# carte_alim.net
KiCad netlist of a schematic drawn in EAGLE
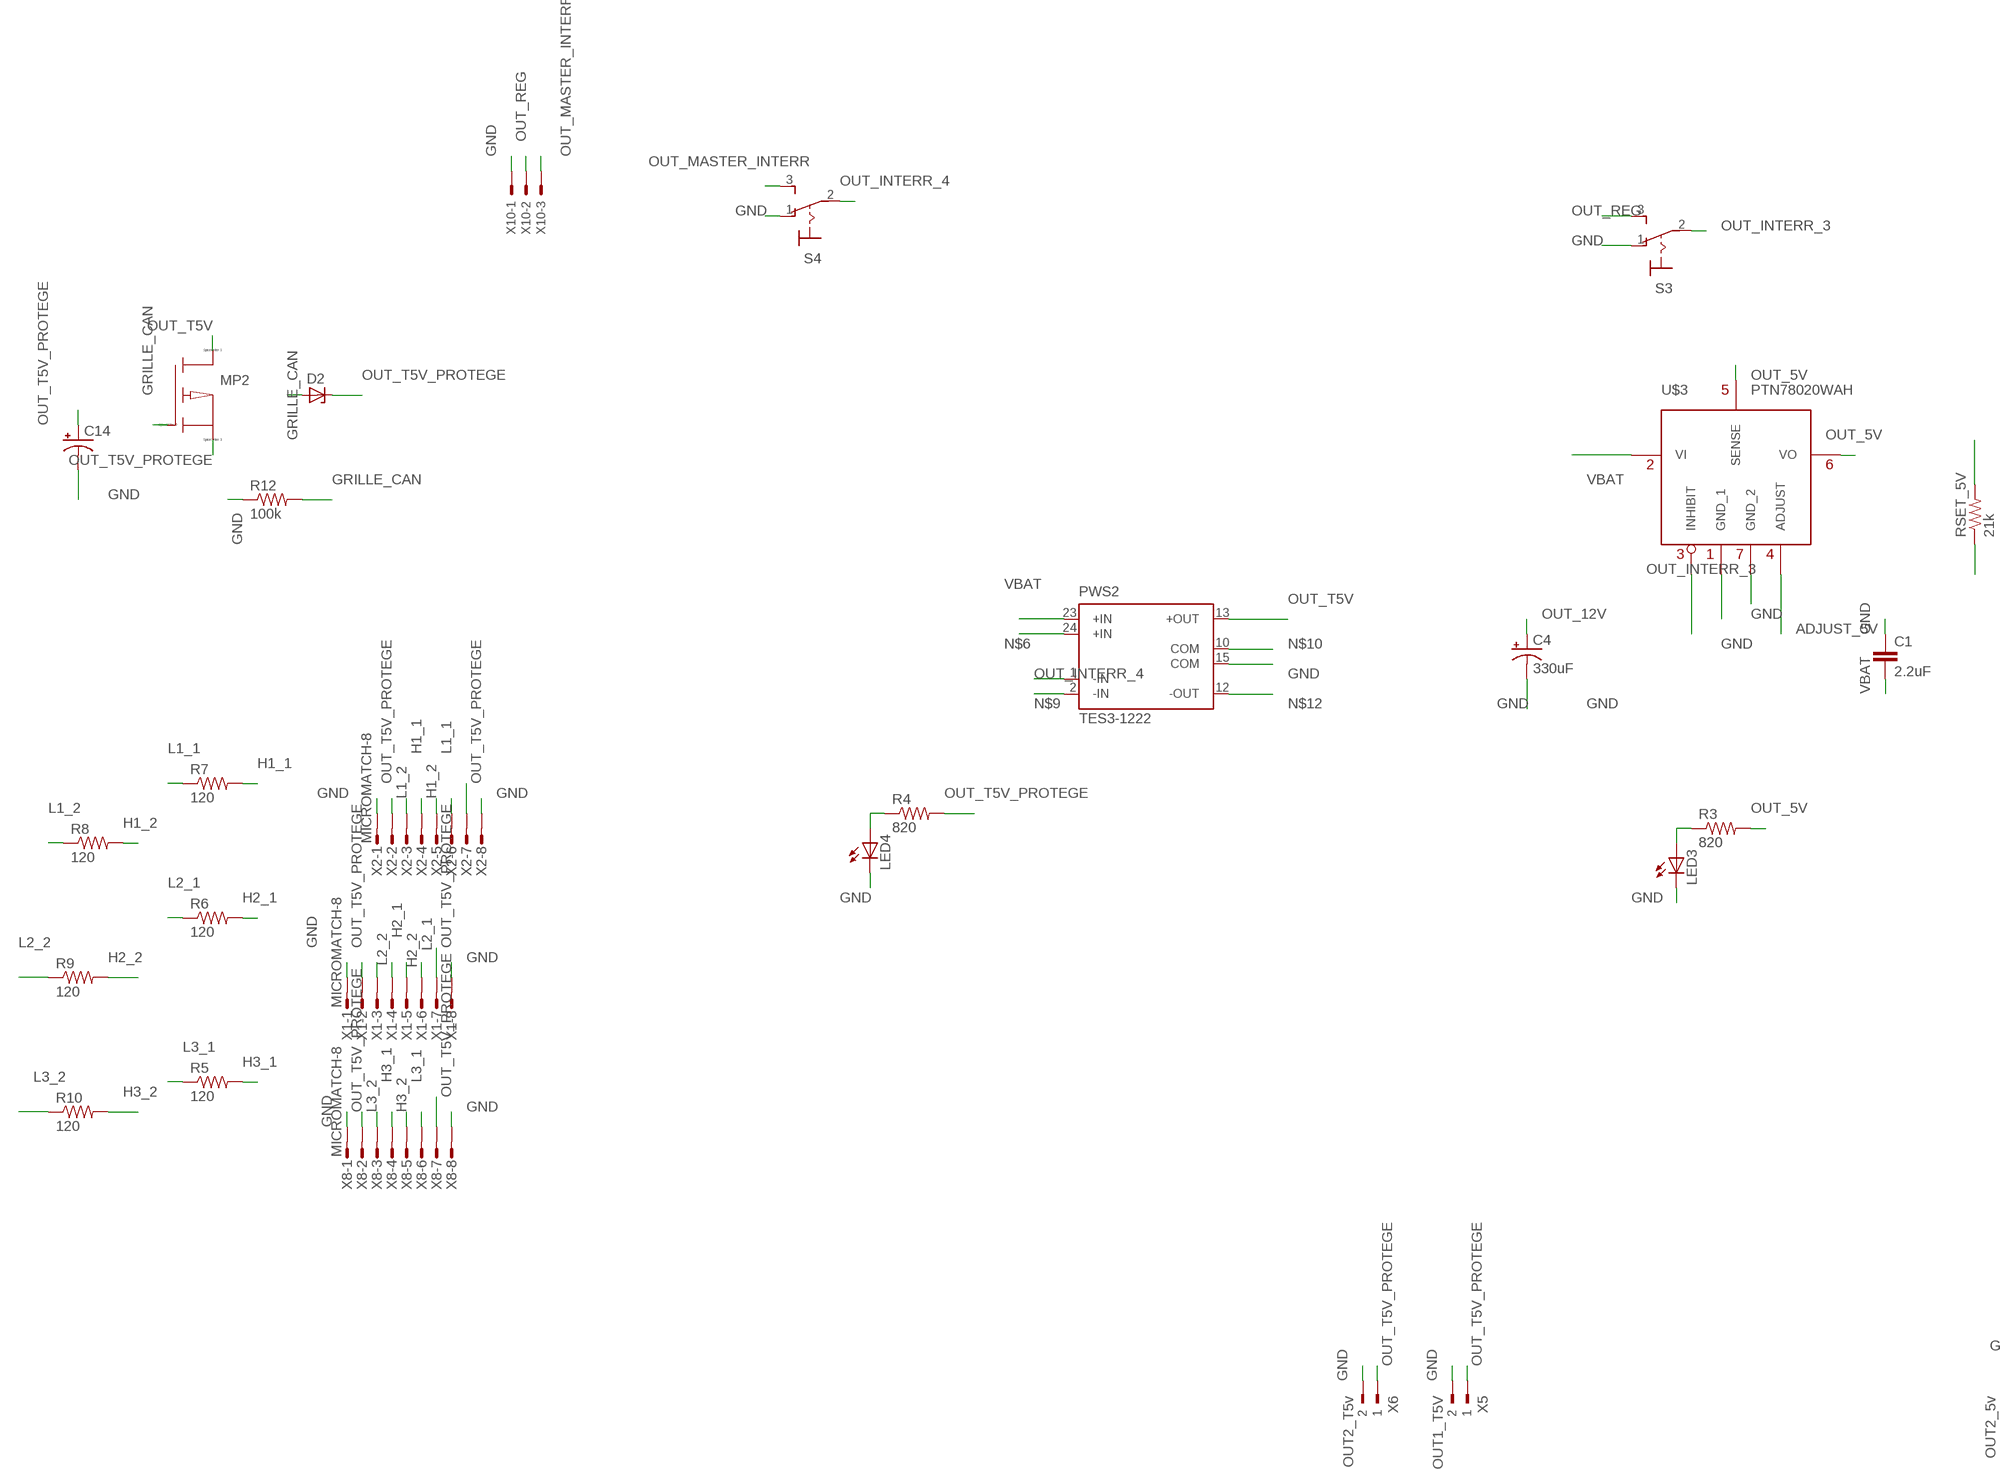
[diagram p0: schematic, sheet 1, part 1 of 2]
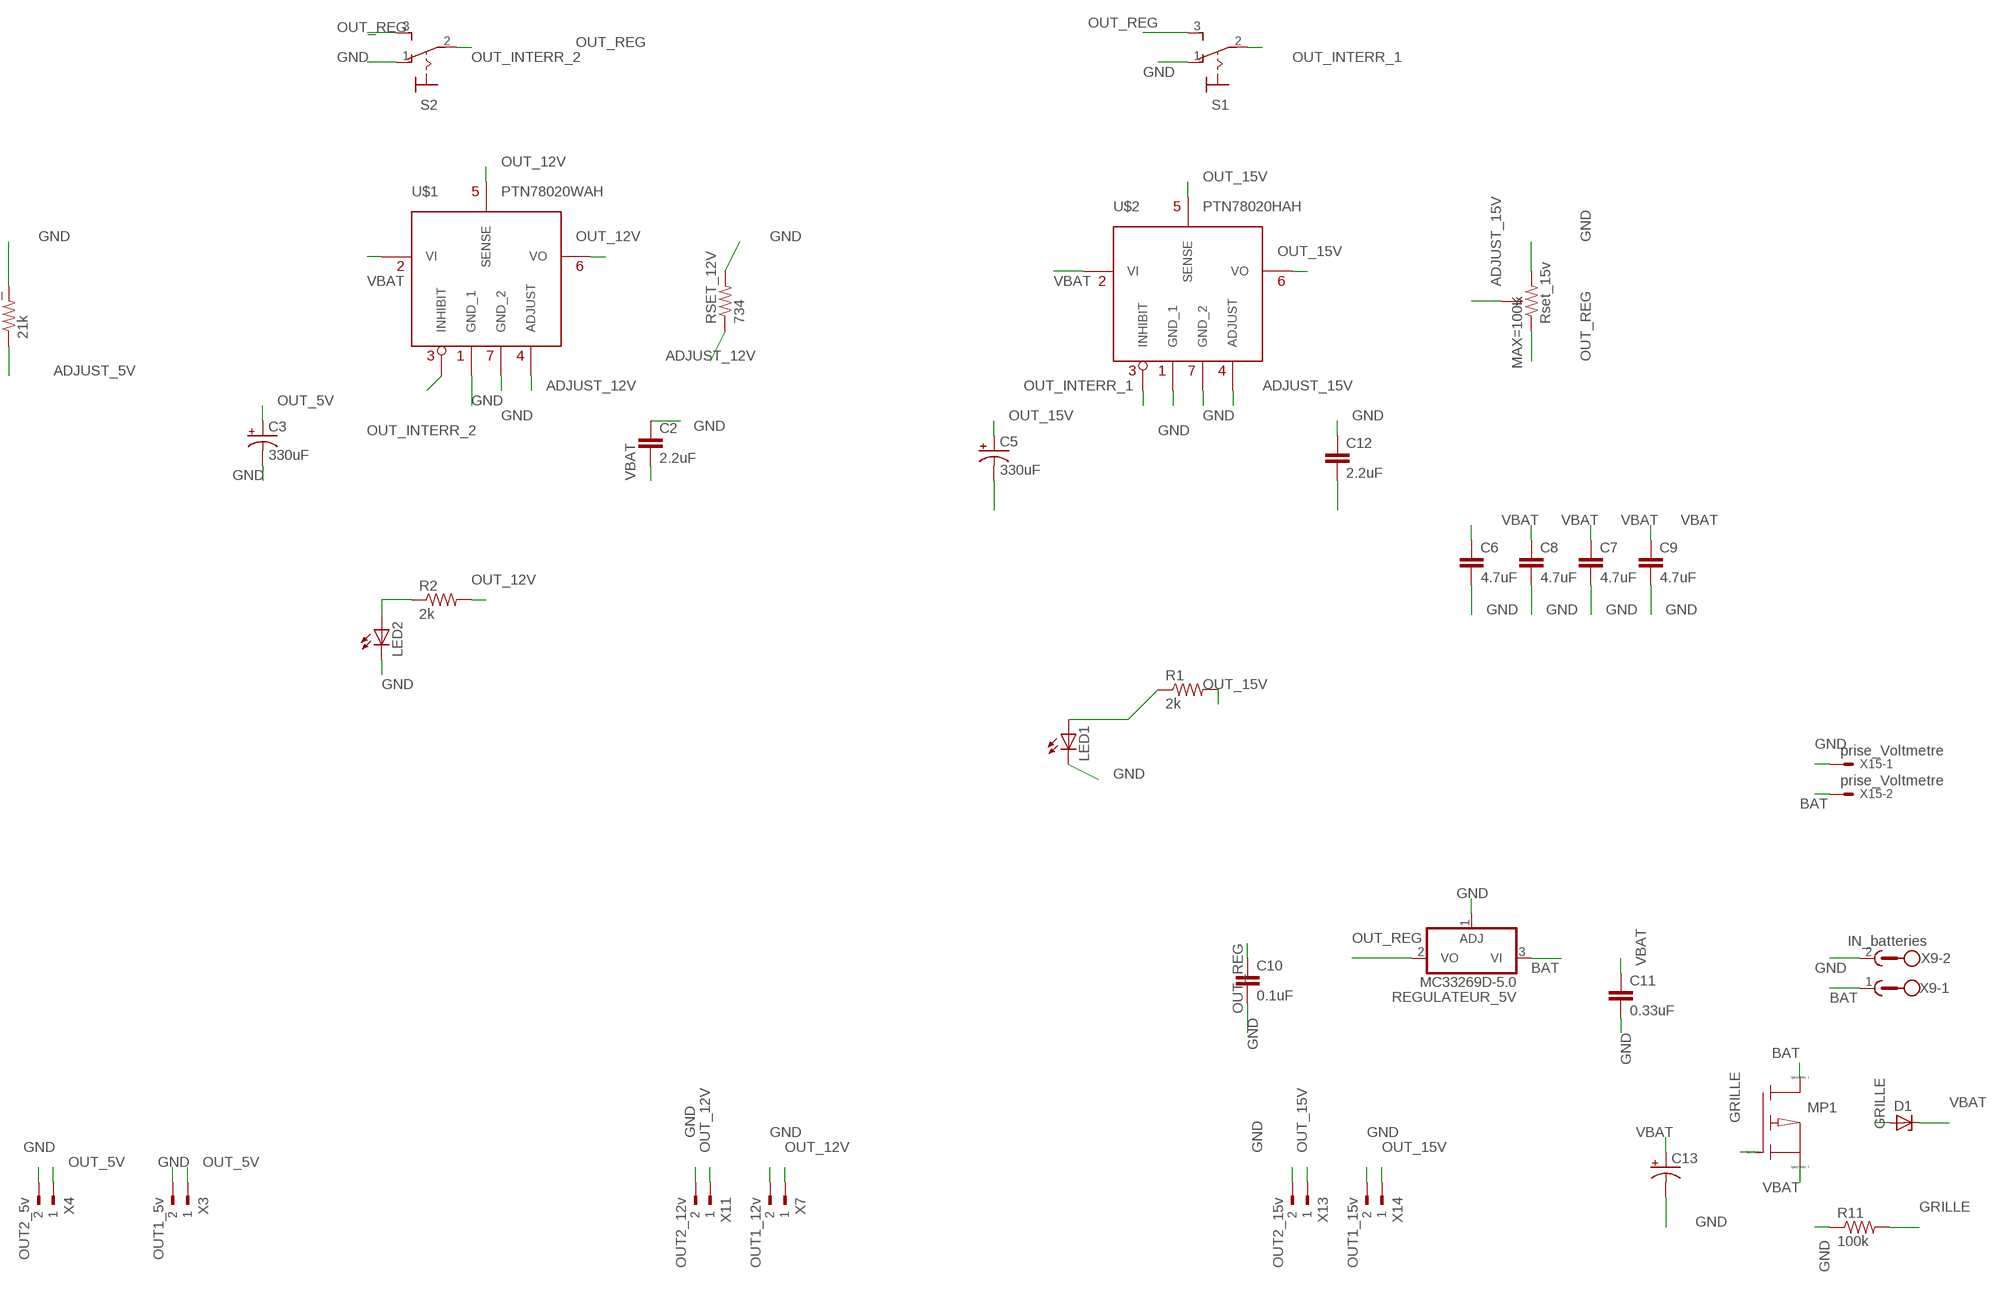
[diagram p1: schematic, sheet 1, part 2 of 2]

(export (version "E")
  (design (tool "Eeschema 10.0.6"))
  (components
    (comp (ref "C1")
      (value "2.2uF")
      (footprint "eagle-import:0805")
      (libsource (lib "eagle-import") (part "CAP0805"))
    )
    (comp (ref "C2")
      (value "2.2uF")
      (footprint "eagle-import:0805")
      (libsource (lib "eagle-import") (part "CAP0805"))
    )
    (comp (ref "C3")
      (value "330uF")
      (footprint "eagle-import:CPOL-RADIAL-100UF-25V")
      (libsource (lib "eagle-import") (part "CAP_POLPTH1"))
    )
    (comp (ref "C4")
      (value "330uF")
      (footprint "eagle-import:CPOL-RADIAL-100UF-25V")
      (libsource (lib "eagle-import") (part "CAP_POLPTH1"))
    )
    (comp (ref "C5")
      (value "330uF")
      (footprint "eagle-import:CPOL-RADIAL-100UF-25V")
      (libsource (lib "eagle-import") (part "CAP_POLPTH1"))
    )
    (comp (ref "C6")
      (value "4.7uF")
      (footprint "eagle-import:0805")
      (libsource (lib "eagle-import") (part "CAP0805"))
    )
    (comp (ref "C7")
      (value "4.7uF")
      (footprint "eagle-import:0805")
      (libsource (lib "eagle-import") (part "CAP0805"))
    )
    (comp (ref "C8")
      (value "4.7uF")
      (footprint "eagle-import:0805")
      (libsource (lib "eagle-import") (part "CAP0805"))
    )
    (comp (ref "C9")
      (value "4.7uF")
      (footprint "eagle-import:0805")
      (libsource (lib "eagle-import") (part "CAP0805"))
    )
    (comp (ref "C10")
      (value "0.1uF")
      (footprint "eagle-import:0805")
      (libsource (lib "eagle-import") (part "CAP0805"))
    )
    (comp (ref "C11")
      (value "0.33uF")
      (footprint "eagle-import:0805")
      (libsource (lib "eagle-import") (part "CAP0805"))
    )
    (comp (ref "C12")
      (value "2.2uF")
      (footprint "eagle-import:0805")
      (libsource (lib "eagle-import") (part "CAP0805"))
    )
    (comp (ref "C13")
      (value "CAP_POLPTH1")
      (footprint "eagle-import:CPOL-RADIAL-100UF-25V")
      (libsource (lib "eagle-import") (part "SparkFun-Passives_CAP_POLPTH1"))
    )
    (comp (ref "C14")
      (value "CAP_POLPTH1")
      (footprint "eagle-import:CPOL-RADIAL-100UF-25V")
      (libsource (lib "eagle-import") (part "SparkFun-Passives_CAP_POLPTH1"))
    )
    (comp (ref "D1")
      (value "ZENER-DIODESOT23")
      (footprint "eagle-import:SOT23")
      (libsource (lib "eagle-import") (part "ZENER-DIODESOT23"))
    )
    (comp (ref "D2")
      (value "ZENER-DIODESOT23")
      (footprint "eagle-import:SOT23")
      (libsource (lib "eagle-import") (part "ZENER-DIODESOT23"))
    )
    (comp (ref "LED1")
      (value "LEDCHIP-LED0805")
      (footprint "eagle-import:CHIP-LED0805")
      (libsource (lib "eagle-import") (part "LEDCHIP-LED0805"))
    )
    (comp (ref "LED2")
      (value "LEDCHIP-LED0805")
      (footprint "eagle-import:CHIP-LED0805")
      (libsource (lib "eagle-import") (part "LEDCHIP-LED0805"))
    )
    (comp (ref "LED3")
      (value "LEDCHIP-LED0805")
      (footprint "eagle-import:CHIP-LED0805")
      (libsource (lib "eagle-import") (part "LEDCHIP-LED0805"))
    )
    (comp (ref "LED4")
      (value "LEDCHIP-LED0805")
      (footprint "eagle-import:CHIP-LED0805")
      (libsource (lib "eagle-import") (part "LEDCHIP-LED0805"))
    )
    (comp (ref "MAX=100K")
      (value "Rset_15v")
      (footprint "eagle-import:3386U")
      (libsource (lib "eagle-import") (part "TRIMPOT-PTH-KNOB"))
    )
    (comp (ref "MP1")
      (value "PMOS")
      (footprint "eagle-import:SOT23")
      (libsource (lib "eagle-import") (part "PMOS"))
    )
    (comp (ref "MP2")
      (value "PMOS")
      (footprint "eagle-import:SOT23")
      (libsource (lib "eagle-import") (part "PMOS"))
    )
    (comp (ref "PWS2")
      (value "TES3-1222")
      (footprint "eagle-import:TES3")
      (libsource (lib "eagle-import") (part "TES3-1222"))
    )
    (comp (ref "R1")
      (value "2k")
      (footprint "eagle-import:0805")
      (libsource (lib "eagle-import") (part "SparkFun-Resistors_RESISTOR0805-RES"))
    )
    (comp (ref "R2")
      (value "2k")
      (footprint "eagle-import:0805")
      (libsource (lib "eagle-import") (part "SparkFun-Resistors_RESISTOR0805-RES"))
    )
    (comp (ref "R3")
      (value "820")
      (footprint "eagle-import:0805")
      (libsource (lib "eagle-import") (part "SparkFun-Resistors_RESISTOR0805-RES"))
    )
    (comp (ref "R4")
      (value "820")
      (footprint "eagle-import:0805")
      (libsource (lib "eagle-import") (part "SparkFun-Resistors_RESISTOR0805-RES"))
    )
    (comp (ref "R5")
      (value "120")
      (footprint "eagle-import:0805")
      (libsource (lib "eagle-import") (part "SparkFun-Resistors_RESISTOR0805-RES"))
    )
    (comp (ref "R6")
      (value "120")
      (footprint "eagle-import:0805")
      (libsource (lib "eagle-import") (part "SparkFun-Resistors_RESISTOR0805-RES"))
    )
    (comp (ref "R7")
      (value "120")
      (footprint "eagle-import:0805")
      (libsource (lib "eagle-import") (part "SparkFun-Resistors_RESISTOR0805-RES"))
    )
    (comp (ref "R8")
      (value "120")
      (footprint "eagle-import:0805")
      (libsource (lib "eagle-import") (part "SparkFun-Resistors_RESISTOR0805-RES"))
    )
    (comp (ref "R9")
      (value "120")
      (footprint "eagle-import:0805")
      (libsource (lib "eagle-import") (part "SparkFun-Resistors_RESISTOR0805-RES"))
    )
    (comp (ref "R10")
      (value "120")
      (footprint "eagle-import:0805")
      (libsource (lib "eagle-import") (part "SparkFun-Resistors_RESISTOR0805-RES"))
    )
    (comp (ref "R11")
      (value "100k")
      (footprint "eagle-import:0805")
      (libsource (lib "eagle-import") (part "RESISTOR0805-RES"))
    )
    (comp (ref "R12")
      (value "100k")
      (footprint "eagle-import:0805")
      (libsource (lib "eagle-import") (part "RESISTOR0805-RES"))
    )
    (comp (ref "REGULATEUR_5V")
      (value "MC33269D-5.0")
      (footprint "eagle-import:DPACK")
      (libsource (lib "eagle-import") (part "MC33269?D-5.0"))
    )
    (comp (ref "RSET_5V")
      (value "21k")
      (footprint "eagle-import:0805")
      (libsource (lib "eagle-import") (part "RESISTOR0805-RES"))
    )
    (comp (ref "RSET_12V")
      (value "734")
      (footprint "eagle-import:0805")
      (libsource (lib "eagle-import") (part "RESISTOR0805-RES"))
    )
    (comp (ref "S1")
      (value "M9040P")
      (footprint "eagle-import:M9040P")
      (libsource (lib "eagle-import") (part "M9040P"))
    )
    (comp (ref "S2")
      (value "M9040P")
      (footprint "eagle-import:M9040P")
      (libsource (lib "eagle-import") (part "M9040P"))
    )
    (comp (ref "S3")
      (value "M9040P")
      (footprint "eagle-import:M9040P")
      (libsource (lib "eagle-import") (part "M9040P"))
    )
    (comp (ref "S4")
      (value "M9040P")
      (footprint "eagle-import:M9040P")
      (libsource (lib "eagle-import") (part "M9040P"))
    )
    (comp (ref "U$1")
      (value "PTN78020WAH")
      (footprint "eagle-import:PTN78060WAH")
      (libsource (lib "eagle-import") (part "PTN78060WAH"))
    )
    (comp (ref "U$2")
      (value "PTN78020HAH")
      (footprint "eagle-import:PTN78060WAH")
      (libsource (lib "eagle-import") (part "PTN78060WAH"))
    )
    (comp (ref "U$3")
      (value "PTN78020WAH")
      (footprint "eagle-import:PTN78060WAH")
      (libsource (lib "eagle-import") (part "PTN78060WAH"))
    )
    (comp (ref "X1")
      (value "MICROMATCH-8")
      (footprint "eagle-import:MICROMATCH-8")
      (fields (field (name "MF") "FARNELL") (field (name "MPN") "7-215464-8"))
      (libsource (lib "eagle-import") (part "MICROMATCH-8"))
    )
    (comp (ref "X2")
      (value "MICROMATCH-8")
      (footprint "eagle-import:MICROMATCH-8")
      (fields (field (name "MF") "FARNELL") (field (name "MPN") "7-215464-8"))
      (libsource (lib "eagle-import") (part "MICROMATCH-8"))
    )
    (comp (ref "X3")
      (value "OUT1_5v")
      (footprint "eagle-import:90-2")
      (libsource (lib "eagle-import") (part "90-2"))
    )
    (comp (ref "X4")
      (value "OUT2_5v")
      (footprint "eagle-import:90-2")
      (libsource (lib "eagle-import") (part "90-2"))
    )
    (comp (ref "X5")
      (value "OUT1_T5V")
      (footprint "eagle-import:90-2")
      (libsource (lib "eagle-import") (part "90-2"))
    )
    (comp (ref "X6")
      (value "OUT2_T5v")
      (footprint "eagle-import:90-2")
      (libsource (lib "eagle-import") (part "90-2"))
    )
    (comp (ref "X7")
      (value "OUT1_12v")
      (footprint "eagle-import:90-2")
      (libsource (lib "eagle-import") (part "90-2"))
    )
    (comp (ref "X8")
      (value "MICROMATCH-8")
      (footprint "eagle-import:MICROMATCH-8")
      (fields (field (name "MF") "FARNELL") (field (name "MPN") "7-215464-8"))
      (libsource (lib "eagle-import") (part "MICROMATCH-8"))
    )
    (comp (ref "X9")
      (value "IN_batteries")
      (footprint "eagle-import:GMSTBA2")
      (fields (field (name "MF") "FARNELL") (field (name "MPN") "1757242"))
      (libsource (lib "eagle-import") (part "GMSTBA2"))
    )
    (comp (ref "X10")
      (value "KK-156-3")
      (footprint "eagle-import:KK-156-3")
      (libsource (lib "eagle-import") (part "KK-156-3"))
    )
    (comp (ref "X11")
      (value "OUT2_12v")
      (footprint "eagle-import:90-2")
      (libsource (lib "eagle-import") (part "90-2"))
    )
    (comp (ref "X13")
      (value "OUT2_15v")
      (footprint "eagle-import:90-2")
      (libsource (lib "eagle-import") (part "90-2"))
    )
    (comp (ref "X14")
      (value "OUT1_15v")
      (footprint "eagle-import:90-2")
      (libsource (lib "eagle-import") (part "90-2"))
    )
    (comp (ref "X15")
      (value "prise_Voltmetre")
      (footprint "eagle-import:KK-156-2")
      (libsource (lib "eagle-import") (part "KK-156-2"))
    )
  )
  (nets
    (net (code "1") (name "/ADJUST_5V") (class "Default")
      (node (ref "RSET_5V") (pin "1") (pinfunction "1_1") (pintype "passive"))
      (node (ref "U$3") (pin "4") (pinfunction "ADJUST_4") (pintype "bidirectional"))
    )
    (net (code "2") (name "/ADJUST_12V") (class "Default")
      (node (ref "RSET_12V") (pin "1") (pinfunction "1_1") (pintype "passive"))
      (node (ref "U$1") (pin "4") (pinfunction "ADJUST_4") (pintype "bidirectional"))
    )
    (net (code "3") (name "/ADJUST_15V") (class "Default")
      (node (ref "MAX=100K") (pin "2") (pinfunction "WIPER_2") (pintype "passive"))
      (node (ref "U$2") (pin "4") (pinfunction "ADJUST_4") (pintype "bidirectional"))
    )
    (net (code "4") (name "/BAT") (class "Default")
      (node (ref "MP1") (pin "3") (pinfunction "D_3") (pintype "passive"))
      (node (ref "REGULATEUR_5V") (pin "3") (pinfunction "VI_3") (pintype "input"))
      (node (ref "X15") (pin "2") (pinfunction "S_2") (pintype "passive"))
      (node (ref "X9") (pin "1") (pinfunction "1_1") (pintype "passive"))
    )
    (net (code "5") (name "/GND") (class "Default")
      (node (ref "C1") (pin "1") (pinfunction "1_1") (pintype "passive"))
      (node (ref "C10") (pin "2") (pinfunction "2_2") (pintype "passive"))
      (node (ref "C11") (pin "2") (pinfunction "2_2") (pintype "passive"))
      (node (ref "C12") (pin "1") (pinfunction "1_1") (pintype "passive"))
      (node (ref "C13") (pin "2") (pinfunction "-_2") (pintype "passive"))
      (node (ref "C14") (pin "2") (pinfunction "-_2") (pintype "passive"))
      (node (ref "C2") (pin "1") (pinfunction "1_1") (pintype "passive"))
      (node (ref "C3") (pin "2") (pinfunction "-_2") (pintype "passive"))
      (node (ref "C4") (pin "2") (pinfunction "-_2") (pintype "passive"))
      (node (ref "C5") (pin "2") (pinfunction "-_2") (pintype "passive"))
      (node (ref "C6") (pin "2") (pinfunction "2_2") (pintype "passive"))
      (node (ref "C7") (pin "2") (pinfunction "2_2") (pintype "passive"))
      (node (ref "C8") (pin "2") (pinfunction "2_2") (pintype "passive"))
      (node (ref "C9") (pin "2") (pinfunction "2_2") (pintype "passive"))
      (node (ref "LED1") (pin "C") (pinfunction "C_C") (pintype "passive"))
      (node (ref "LED2") (pin "C") (pinfunction "C_C") (pintype "passive"))
      (node (ref "LED3") (pin "C") (pinfunction "C_C") (pintype "passive"))
      (node (ref "LED4") (pin "C") (pinfunction "C_C") (pintype "passive"))
      (node (ref "MAX=100K") (pin "3") (pinfunction "CW_3") (pintype "passive"))
      (node (ref "PWS2") (pin "15") (pinfunction "COM_15") (pintype "passive"))
      (node (ref "R11") (pin "1") (pinfunction "1_1") (pintype "passive"))
      (node (ref "R12") (pin "1") (pinfunction "1_1") (pintype "passive"))
      (node (ref "REGULATEUR_5V") (pin "1") (pinfunction "ADJ_1") (pintype "input"))
      (node (ref "RSET_12V") (pin "2") (pinfunction "2_2") (pintype "passive"))
      (node (ref "RSET_5V") (pin "2") (pinfunction "2_2") (pintype "passive"))
      (node (ref "S1") (pin "1") (pinfunction "O_1") (pintype "passive"))
      (node (ref "S2") (pin "1") (pinfunction "O_1") (pintype "passive"))
      (node (ref "S3") (pin "1") (pinfunction "O_1") (pintype "passive"))
      (node (ref "S4") (pin "1") (pinfunction "O_1") (pintype "passive"))
      (node (ref "U$1") (pin "1") (pinfunction "GND_1_1") (pintype "bidirectional"))
      (node (ref "U$1") (pin "7") (pinfunction "GND_2_7") (pintype "bidirectional"))
      (node (ref "U$2") (pin "1") (pinfunction "GND_1_1") (pintype "bidirectional"))
      (node (ref "U$2") (pin "7") (pinfunction "GND_2_7") (pintype "bidirectional"))
      (node (ref "U$3") (pin "1") (pinfunction "GND_1_1") (pintype "bidirectional"))
      (node (ref "U$3") (pin "7") (pinfunction "GND_2_7") (pintype "bidirectional"))
      (node (ref "X1") (pin "1") (pinfunction "S_1") (pintype "passive"))
      (node (ref "X1") (pin "8") (pinfunction "S_8") (pintype "passive"))
      (node (ref "X10") (pin "1") (pinfunction "S_1") (pintype "passive"))
      (node (ref "X11") (pin "2") (pinfunction "2_2") (pintype "passive"))
      (node (ref "X13") (pin "2") (pinfunction "2_2") (pintype "passive"))
      (node (ref "X14") (pin "2") (pinfunction "2_2") (pintype "passive"))
      (node (ref "X15") (pin "1") (pinfunction "S_1") (pintype "passive"))
      (node (ref "X2") (pin "1") (pinfunction "S_1") (pintype "passive"))
      (node (ref "X2") (pin "8") (pinfunction "S_8") (pintype "passive"))
      (node (ref "X3") (pin "2") (pinfunction "2_2") (pintype "passive"))
      (node (ref "X4") (pin "2") (pinfunction "2_2") (pintype "passive"))
      (node (ref "X5") (pin "2") (pinfunction "2_2") (pintype "passive"))
      (node (ref "X6") (pin "2") (pinfunction "2_2") (pintype "passive"))
      (node (ref "X7") (pin "2") (pinfunction "2_2") (pintype "passive"))
      (node (ref "X8") (pin "1") (pinfunction "S_1") (pintype "passive"))
      (node (ref "X8") (pin "8") (pinfunction "S_8") (pintype "passive"))
      (node (ref "X9") (pin "2") (pinfunction "1_2") (pintype "passive"))
    )
    (net (code "6") (name "/GRILLE") (class "Default")
      (node (ref "D1") (pin "1") (pinfunction "A_1") (pintype "passive"))
      (node (ref "MP1") (pin "1") (pinfunction "G_1") (pintype "passive"))
      (node (ref "R11") (pin "2") (pinfunction "2_2") (pintype "passive"))
    )
    (net (code "7") (name "/GRILLE_CAN") (class "Default")
      (node (ref "D2") (pin "1") (pinfunction "A_1") (pintype "passive"))
      (node (ref "MP2") (pin "1") (pinfunction "G_1") (pintype "passive"))
      (node (ref "R12") (pin "2") (pinfunction "2_2") (pintype "passive"))
    )
    (net (code "8") (name "/H1_1") (class "Default")
      (node (ref "R7") (pin "2") (pinfunction "2_2") (pintype "passive"))
      (node (ref "X2") (pin "4") (pinfunction "S_4") (pintype "passive"))
    )
    (net (code "9") (name "/H1_2") (class "Default")
      (node (ref "R8") (pin "2") (pinfunction "2_2") (pintype "passive"))
      (node (ref "X2") (pin "5") (pinfunction "S_5") (pintype "passive"))
    )
    (net (code "10") (name "/H2_1") (class "Default")
      (node (ref "R6") (pin "2") (pinfunction "2_2") (pintype "passive"))
      (node (ref "X1") (pin "4") (pinfunction "S_4") (pintype "passive"))
    )
    (net (code "11") (name "/H2_2") (class "Default")
      (node (ref "R9") (pin "2") (pinfunction "2_2") (pintype "passive"))
      (node (ref "X1") (pin "5") (pinfunction "S_5") (pintype "passive"))
    )
    (net (code "12") (name "/H3_1") (class "Default")
      (node (ref "R5") (pin "2") (pinfunction "2_2") (pintype "passive"))
      (node (ref "X8") (pin "4") (pinfunction "S_4") (pintype "passive"))
    )
    (net (code "13") (name "/H3_2") (class "Default")
      (node (ref "R10") (pin "2") (pinfunction "2_2") (pintype "passive"))
      (node (ref "X8") (pin "5") (pinfunction "S_5") (pintype "passive"))
    )
    (net (code "14") (name "/L1_1") (class "Default")
      (node (ref "R7") (pin "1") (pinfunction "1_1") (pintype "passive"))
      (node (ref "X2") (pin "6") (pinfunction "S_6") (pintype "passive"))
    )
    (net (code "15") (name "/L1_2") (class "Default")
      (node (ref "R8") (pin "1") (pinfunction "1_1") (pintype "passive"))
      (node (ref "X2") (pin "3") (pinfunction "S_3") (pintype "passive"))
    )
    (net (code "16") (name "/L2_1") (class "Default")
      (node (ref "R6") (pin "1") (pinfunction "1_1") (pintype "passive"))
      (node (ref "X1") (pin "6") (pinfunction "S_6") (pintype "passive"))
    )
    (net (code "17") (name "/L2_2") (class "Default")
      (node (ref "R9") (pin "1") (pinfunction "1_1") (pintype "passive"))
      (node (ref "X1") (pin "3") (pinfunction "S_3") (pintype "passive"))
    )
    (net (code "18") (name "/L3_1") (class "Default")
      (node (ref "R5") (pin "1") (pinfunction "1_1") (pintype "passive"))
      (node (ref "X8") (pin "6") (pinfunction "S_6") (pintype "passive"))
    )
    (net (code "19") (name "/L3_2") (class "Default")
      (node (ref "R10") (pin "1") (pinfunction "1_1") (pintype "passive"))
      (node (ref "X8") (pin "3") (pinfunction "S_3") (pintype "passive"))
    )
    (net (code "20") (name "/N$6") (class "Default")
      (node (ref "PWS2") (pin "24") (pinfunction "+IN_24") (pintype "input"))
    )
    (net (code "21") (name "/N$9") (class "Default")
      (node (ref "PWS2") (pin "2") (pinfunction "-IN_2") (pintype "input"))
    )
    (net (code "22") (name "/N$10") (class "Default")
      (node (ref "PWS2") (pin "10") (pinfunction "COM_10") (pintype "passive"))
    )
    (net (code "23") (name "/N$12") (class "Default")
      (node (ref "PWS2") (pin "12") (pinfunction "-OUT_12") (pintype "output"))
    )
    (net (code "24") (name "/OUT_5V") (class "Default")
      (node (ref "C3") (pin "1") (pinfunction "+_1") (pintype "passive"))
      (node (ref "R3") (pin "2") (pinfunction "2_2") (pintype "passive"))
      (node (ref "U$3") (pin "5") (pinfunction "SENSE_5") (pintype "bidirectional"))
      (node (ref "U$3") (pin "6") (pinfunction "VO_6") (pintype "bidirectional"))
      (node (ref "X3") (pin "1") (pinfunction "1_1") (pintype "passive"))
      (node (ref "X4") (pin "1") (pinfunction "1_1") (pintype "passive"))
    )
    (net (code "25") (name "/OUT_12V") (class "Default")
      (node (ref "C4") (pin "1") (pinfunction "+_1") (pintype "passive"))
      (node (ref "R2") (pin "2") (pinfunction "2_2") (pintype "passive"))
      (node (ref "U$1") (pin "5") (pinfunction "SENSE_5") (pintype "bidirectional"))
      (node (ref "U$1") (pin "6") (pinfunction "VO_6") (pintype "bidirectional"))
      (node (ref "X11") (pin "1") (pinfunction "1_1") (pintype "passive"))
      (node (ref "X7") (pin "1") (pinfunction "1_1") (pintype "passive"))
    )
    (net (code "26") (name "/OUT_15V") (class "Default")
      (node (ref "C5") (pin "1") (pinfunction "+_1") (pintype "passive"))
      (node (ref "R1") (pin "2") (pinfunction "2_2") (pintype "passive"))
      (node (ref "U$2") (pin "5") (pinfunction "SENSE_5") (pintype "bidirectional"))
      (node (ref "U$2") (pin "6") (pinfunction "VO_6") (pintype "bidirectional"))
      (node (ref "X13") (pin "1") (pinfunction "1_1") (pintype "passive"))
      (node (ref "X14") (pin "1") (pinfunction "1_1") (pintype "passive"))
    )
    (net (code "27") (name "/OUT_INTERR_1") (class "Default")
      (node (ref "S1") (pin "2") (pinfunction "P_2") (pintype "passive"))
      (node (ref "U$2") (pin "3") (pinfunction "INHIBIT_3") (pintype "bidirectional"))
    )
    (net (code "28") (name "/OUT_INTERR_2") (class "Default")
      (node (ref "S2") (pin "2") (pinfunction "P_2") (pintype "passive"))
      (node (ref "U$1") (pin "3") (pinfunction "INHIBIT_3") (pintype "bidirectional"))
    )
    (net (code "29") (name "/OUT_INTERR_3") (class "Default")
      (node (ref "S3") (pin "2") (pinfunction "P_2") (pintype "passive"))
      (node (ref "U$3") (pin "3") (pinfunction "INHIBIT_3") (pintype "bidirectional"))
    )
    (net (code "30") (name "/OUT_INTERR_4") (class "Default")
      (node (ref "PWS2") (pin "1") (pinfunction "-IN_1") (pintype "input"))
      (node (ref "S4") (pin "2") (pinfunction "P_2") (pintype "passive"))
    )
    (net (code "31") (name "/OUT_MASTER_INTERR") (class "Default")
      (node (ref "S4") (pin "3") (pinfunction "S_3") (pintype "passive"))
      (node (ref "X10") (pin "3") (pinfunction "S_3") (pintype "passive"))
    )
    (net (code "32") (name "/OUT_REG") (class "Default")
      (node (ref "C10") (pin "1") (pinfunction "1_1") (pintype "passive"))
      (node (ref "MAX=100K") (pin "1") (pinfunction "CCW_1") (pintype "passive"))
      (node (ref "REGULATEUR_5V") (pin "2") (pinfunction "VO_2") (pintype "passive"))
      (node (ref "S1") (pin "3") (pinfunction "S_3") (pintype "passive"))
      (node (ref "S2") (pin "3") (pinfunction "S_3") (pintype "passive"))
      (node (ref "S3") (pin "3") (pinfunction "S_3") (pintype "passive"))
      (node (ref "X10") (pin "2") (pinfunction "S_2") (pintype "passive"))
    )
    (net (code "33") (name "/OUT_T5V") (class "Default")
      (node (ref "MP2") (pin "3") (pinfunction "D_3") (pintype "passive"))
      (node (ref "PWS2") (pin "13") (pinfunction "+OUT_13") (pintype "output"))
    )
    (net (code "34") (name "/OUT_T5V_PROTEGE") (class "Default")
      (node (ref "C14") (pin "1") (pinfunction "+_1") (pintype "passive"))
      (node (ref "D2") (pin "3") (pinfunction "C_3") (pintype "passive"))
      (node (ref "MP2") (pin "2") (pinfunction "S_2") (pintype "passive"))
      (node (ref "R4") (pin "2") (pinfunction "2_2") (pintype "passive"))
      (node (ref "X1") (pin "2") (pinfunction "S_2") (pintype "passive"))
      (node (ref "X1") (pin "7") (pinfunction "S_7") (pintype "passive"))
      (node (ref "X2") (pin "2") (pinfunction "S_2") (pintype "passive"))
      (node (ref "X2") (pin "7") (pinfunction "S_7") (pintype "passive"))
      (node (ref "X5") (pin "1") (pinfunction "1_1") (pintype "passive"))
      (node (ref "X6") (pin "1") (pinfunction "1_1") (pintype "passive"))
      (node (ref "X8") (pin "2") (pinfunction "S_2") (pintype "passive"))
      (node (ref "X8") (pin "7") (pinfunction "S_7") (pintype "passive"))
    )
    (net (code "35") (name "/VBAT") (class "Default")
      (node (ref "C1") (pin "2") (pinfunction "2_2") (pintype "passive"))
      (node (ref "C11") (pin "1") (pinfunction "1_1") (pintype "passive"))
      (node (ref "C12") (pin "2") (pinfunction "2_2") (pintype "passive"))
      (node (ref "C13") (pin "1") (pinfunction "+_1") (pintype "passive"))
      (node (ref "C2") (pin "2") (pinfunction "2_2") (pintype "passive"))
      (node (ref "C6") (pin "1") (pinfunction "1_1") (pintype "passive"))
      (node (ref "C7") (pin "1") (pinfunction "1_1") (pintype "passive"))
      (node (ref "C8") (pin "1") (pinfunction "1_1") (pintype "passive"))
      (node (ref "C9") (pin "1") (pinfunction "1_1") (pintype "passive"))
      (node (ref "D1") (pin "3") (pinfunction "C_3") (pintype "passive"))
      (node (ref "MP1") (pin "2") (pinfunction "S_2") (pintype "passive"))
      (node (ref "PWS2") (pin "23") (pinfunction "+IN_23") (pintype "input"))
      (node (ref "U$1") (pin "2") (pinfunction "VI_2") (pintype "bidirectional"))
      (node (ref "U$2") (pin "2") (pinfunction "VI_2") (pintype "bidirectional"))
      (node (ref "U$3") (pin "2") (pinfunction "VI_2") (pintype "bidirectional"))
    )
    (net (code "36") (name "Net-(LED1-PadA)") (class "Default")
      (node (ref "LED1") (pin "A") (pinfunction "A_A") (pintype "passive"))
      (node (ref "R1") (pin "1") (pinfunction "1_1") (pintype "passive"))
    )
    (net (code "37") (name "Net-(LED2-PadA)") (class "Default")
      (node (ref "LED2") (pin "A") (pinfunction "A_A") (pintype "passive"))
      (node (ref "R2") (pin "1") (pinfunction "1_1") (pintype "passive"))
    )
    (net (code "38") (name "Net-(LED3-PadA)") (class "Default")
      (node (ref "LED3") (pin "A") (pinfunction "A_A") (pintype "passive"))
      (node (ref "R3") (pin "1") (pinfunction "1_1") (pintype "passive"))
    )
    (net (code "39") (name "Net-(LED4-PadA)") (class "Default")
      (node (ref "LED4") (pin "A") (pinfunction "A_A") (pintype "passive"))
      (node (ref "R4") (pin "1") (pinfunction "1_1") (pintype "passive"))
    )
  )
)
